# ECL.net
KiCad netlist of a schematic drawn in Altium Designer
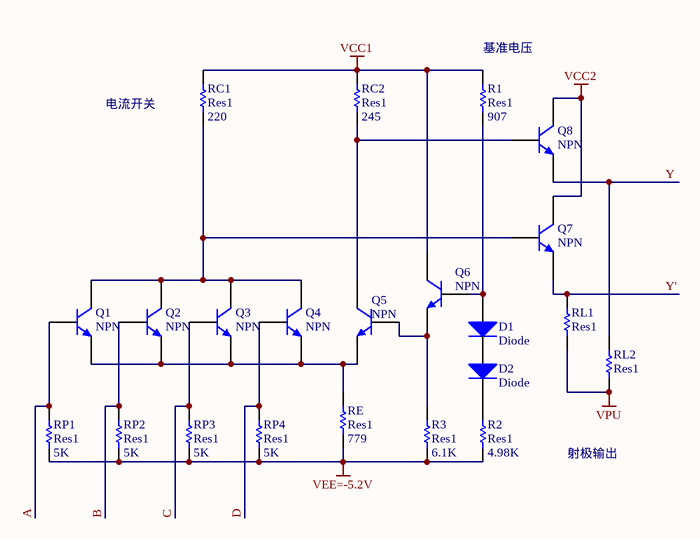
[diagram p0: ECL.SchDoc]

(export (version "E")
  (design (tool "Eeschema 10.0.6"))
  (components
    (comp (ref "D1")
      (value "Diode")
      (footprint "SMC")
      (description "Default Diode")
      (fields (field (name "PUBLISHER") "Altium Limited"))
      (libsource (lib "Miscellaneous Devices") (part "Diode"))
    )
    (comp (ref "D2")
      (value "Diode")
      (footprint "SMC")
      (description "Default Diode")
      (fields (field (name "PUBLISHER") "Altium Limited"))
      (libsource (lib "Miscellaneous Devices") (part "Diode"))
    )
    (comp (ref "Q1")
      (value "NPN")
      (footprint "TO-226-AA")
      (description "NPN Bipolar Transistor")
      (fields (field (name "PUBLISHER") "Altium Limited"))
      (libsource (lib "Miscellaneous Devices") (part "NPN"))
    )
    (comp (ref "Q2")
      (value "NPN")
      (footprint "TO-226-AA")
      (description "NPN Bipolar Transistor")
      (fields (field (name "PUBLISHER") "Altium Limited"))
      (libsource (lib "Miscellaneous Devices") (part "NPN"))
    )
    (comp (ref "Q3")
      (value "NPN")
      (footprint "TO-226-AA")
      (description "NPN Bipolar Transistor")
      (fields (field (name "PUBLISHER") "Altium Limited"))
      (libsource (lib "Miscellaneous Devices") (part "NPN"))
    )
    (comp (ref "Q4")
      (value "NPN")
      (footprint "TO-226-AA")
      (description "NPN Bipolar Transistor")
      (fields (field (name "PUBLISHER") "Altium Limited"))
      (libsource (lib "Miscellaneous Devices") (part "NPN"))
    )
    (comp (ref "Q5")
      (value "NPN")
      (footprint "TO-226-AA")
      (description "NPN Bipolar Transistor")
      (fields (field (name "PUBLISHER") "Altium Limited"))
      (libsource (lib "Miscellaneous Devices") (part "NPN"))
    )
    (comp (ref "Q6")
      (value "NPN")
      (footprint "TO-226-AA")
      (description "NPN Bipolar Transistor")
      (fields (field (name "PUBLISHER") "Altium Limited"))
      (libsource (lib "Miscellaneous Devices") (part "NPN"))
    )
    (comp (ref "Q7")
      (value "NPN")
      (footprint "TO-226-AA")
      (description "NPN Bipolar Transistor")
      (fields (field (name "PUBLISHER") "Altium Limited"))
      (libsource (lib "Miscellaneous Devices") (part "NPN"))
    )
    (comp (ref "Q8")
      (value "NPN")
      (footprint "TO-226-AA")
      (description "NPN Bipolar Transistor")
      (fields (field (name "PUBLISHER") "Altium Limited"))
      (libsource (lib "Miscellaneous Devices") (part "NPN"))
    )
    (comp (ref "R1")
      (value "Res1")
      (footprint "AXIAL-0.3")
      (description "Resistor")
      (fields (field (name "ALTIUM_VALUE") "907") (field (name "PUBLISHER") "Altium Limited"))
      (libsource (lib "Miscellaneous Devices") (part "Res1"))
    )
    (comp (ref "R2")
      (value "Res1")
      (footprint "AXIAL-0.3")
      (description "Resistor")
      (fields (field (name "ALTIUM_VALUE") "4.98K") (field (name "PUBLISHER") "Altium Limited"))
      (libsource (lib "Miscellaneous Devices") (part "Res1"))
    )
    (comp (ref "R3")
      (value "Res1")
      (footprint "AXIAL-0.3")
      (description "Resistor")
      (fields (field (name "ALTIUM_VALUE") "6.1K") (field (name "PUBLISHER") "Altium Limited"))
      (libsource (lib "Miscellaneous Devices") (part "Res1"))
    )
    (comp (ref "RC1")
      (value "Res1")
      (footprint "AXIAL-0.3")
      (description "Resistor")
      (fields (field (name "ALTIUM_VALUE") "220") (field (name "PUBLISHER") "Altium Limited"))
      (libsource (lib "Miscellaneous Devices") (part "Res1"))
    )
    (comp (ref "RC2")
      (value "Res1")
      (footprint "AXIAL-0.3")
      (description "Resistor")
      (fields (field (name "ALTIUM_VALUE") "245") (field (name "PUBLISHER") "Altium Limited"))
      (libsource (lib "Miscellaneous Devices") (part "Res1"))
    )
    (comp (ref "RE")
      (value "Res1")
      (footprint "AXIAL-0.3")
      (description "Resistor")
      (fields (field (name "ALTIUM_VALUE") "779") (field (name "PUBLISHER") "Altium Limited"))
      (libsource (lib "Miscellaneous Devices") (part "Res1"))
    )
    (comp (ref "RL1")
      (value "Res1")
      (footprint "AXIAL-0.3")
      (description "Resistor")
      (fields (field (name "PUBLISHER") "Altium Limited"))
      (libsource (lib "Miscellaneous Devices") (part "Res1"))
    )
    (comp (ref "RL2")
      (value "Res1")
      (footprint "AXIAL-0.3")
      (description "Resistor")
      (fields (field (name "PUBLISHER") "Altium Limited"))
      (libsource (lib "Miscellaneous Devices") (part "Res1"))
    )
    (comp (ref "RP1")
      (value "Res1")
      (footprint "AXIAL-0.3")
      (description "Resistor")
      (fields (field (name "ALTIUM_VALUE") "5K") (field (name "PUBLISHER") "Altium Limited"))
      (libsource (lib "Miscellaneous Devices") (part "Res1"))
    )
    (comp (ref "RP2")
      (value "Res1")
      (footprint "AXIAL-0.3")
      (description "Resistor")
      (fields (field (name "ALTIUM_VALUE") "5K") (field (name "PUBLISHER") "Altium Limited"))
      (libsource (lib "Miscellaneous Devices") (part "Res1"))
    )
    (comp (ref "RP3")
      (value "Res1")
      (footprint "AXIAL-0.3")
      (description "Resistor")
      (fields (field (name "ALTIUM_VALUE") "5K") (field (name "PUBLISHER") "Altium Limited"))
      (libsource (lib "Miscellaneous Devices") (part "Res1"))
    )
    (comp (ref "RP4")
      (value "Res1")
      (footprint "AXIAL-0.3")
      (description "Resistor")
      (fields (field (name "ALTIUM_VALUE") "5K") (field (name "PUBLISHER") "Altium Limited"))
      (libsource (lib "Miscellaneous Devices") (part "Res1"))
    )
  )
  (nets
    (net (code "1") (name "/A") (class "Default")
      (node (ref "Q1") (pin "2") (pinfunction "B_2") (pintype "passive"))
      (node (ref "RP1") (pin "2") (pinfunction "2_2") (pintype "passive"))
    )
    (net (code "2") (name "/B") (class "Default")
      (node (ref "Q2") (pin "2") (pinfunction "B_2") (pintype "passive"))
      (node (ref "RP2") (pin "2") (pinfunction "2_2") (pintype "passive"))
    )
    (net (code "3") (name "/C") (class "Default")
      (node (ref "Q3") (pin "2") (pinfunction "B_2") (pintype "passive"))
      (node (ref "RP3") (pin "2") (pinfunction "2_2") (pintype "passive"))
    )
    (net (code "4") (name "/D") (class "Default")
      (node (ref "Q4") (pin "2") (pinfunction "B_2") (pintype "passive"))
      (node (ref "RP4") (pin "2") (pinfunction "2_2") (pintype "passive"))
    )
    (net (code "5") (name "/Y") (class "Default")
      (node (ref "Q8") (pin "3") (pinfunction "E_3") (pintype "passive"))
      (node (ref "RL2") (pin "2") (pinfunction "2_2") (pintype "passive"))
    )
    (net (code "6") (name "/Y'") (class "Default")
      (node (ref "Q7") (pin "3") (pinfunction "E_3") (pintype "passive"))
      (node (ref "RL1") (pin "2") (pinfunction "2_2") (pintype "passive"))
    )
    (net (code "7") (name "Net-(D1-A)") (class "Default")
      (node (ref "D1") (pin "1") (pinfunction "A_1") (pintype "passive"))
      (node (ref "Q6") (pin "2") (pinfunction "B_2") (pintype "passive"))
      (node (ref "R1") (pin "1") (pinfunction "1_1") (pintype "passive"))
    )
    (net (code "8") (name "Net-(D2-K)") (class "Default")
      (node (ref "D2") (pin "2") (pinfunction "K_2") (pintype "passive"))
      (node (ref "R2") (pin "2") (pinfunction "2_2") (pintype "passive"))
    )
    (net (code "9") (name "Net-(Q1-C)") (class "Default")
      (node (ref "Q1") (pin "1") (pinfunction "C_1") (pintype "passive"))
      (node (ref "Q2") (pin "1") (pinfunction "C_1") (pintype "passive"))
      (node (ref "Q3") (pin "1") (pinfunction "C_1") (pintype "passive"))
      (node (ref "Q4") (pin "1") (pinfunction "C_1") (pintype "passive"))
      (node (ref "Q7") (pin "2") (pinfunction "B_2") (pintype "passive"))
      (node (ref "RC1") (pin "1") (pinfunction "1_1") (pintype "passive"))
    )
    (net (code "10") (name "Net-(Q1-E)") (class "Default")
      (node (ref "Q1") (pin "3") (pinfunction "E_3") (pintype "passive"))
      (node (ref "Q2") (pin "3") (pinfunction "E_3") (pintype "passive"))
      (node (ref "Q3") (pin "3") (pinfunction "E_3") (pintype "passive"))
      (node (ref "Q4") (pin "3") (pinfunction "E_3") (pintype "passive"))
      (node (ref "Q5") (pin "3") (pinfunction "E_3") (pintype "passive"))
      (node (ref "RE") (pin "2") (pinfunction "2_2") (pintype "passive"))
    )
    (net (code "11") (name "Net-(Q5-B)") (class "Default")
      (node (ref "Q5") (pin "2") (pinfunction "B_2") (pintype "passive"))
      (node (ref "Q6") (pin "3") (pinfunction "E_3") (pintype "passive"))
      (node (ref "R3") (pin "2") (pinfunction "2_2") (pintype "passive"))
    )
    (net (code "12") (name "Net-(Q5-C)") (class "Default")
      (node (ref "Q5") (pin "1") (pinfunction "C_1") (pintype "passive"))
      (node (ref "Q8") (pin "2") (pinfunction "B_2") (pintype "passive"))
      (node (ref "RC2") (pin "1") (pinfunction "1_1") (pintype "passive"))
    )
    (net (code "13") (name "VCC1") (class "Default")
      (node (ref "Q6") (pin "1") (pinfunction "C_1") (pintype "passive"))
      (node (ref "R1") (pin "2") (pinfunction "2_2") (pintype "passive"))
      (node (ref "RC1") (pin "2") (pinfunction "2_2") (pintype "passive"))
      (node (ref "RC2") (pin "2") (pinfunction "2_2") (pintype "passive"))
    )
    (net (code "14") (name "VCC2") (class "Default")
      (node (ref "Q7") (pin "1") (pinfunction "C_1") (pintype "passive"))
      (node (ref "Q8") (pin "1") (pinfunction "C_1") (pintype "passive"))
    )
    (net (code "15") (name "VEE=-5.2V") (class "Default")
      (node (ref "R2") (pin "1") (pinfunction "1_1") (pintype "passive"))
      (node (ref "R3") (pin "1") (pinfunction "1_1") (pintype "passive"))
      (node (ref "RE") (pin "1") (pinfunction "1_1") (pintype "passive"))
      (node (ref "RP1") (pin "1") (pinfunction "1_1") (pintype "passive"))
      (node (ref "RP2") (pin "1") (pinfunction "1_1") (pintype "passive"))
      (node (ref "RP3") (pin "1") (pinfunction "1_1") (pintype "passive"))
      (node (ref "RP4") (pin "1") (pinfunction "1_1") (pintype "passive"))
    )
    (net (code "16") (name "VPU") (class "Default")
      (node (ref "RL1") (pin "1") (pinfunction "1_1") (pintype "passive"))
      (node (ref "RL2") (pin "1") (pinfunction "1_1") (pintype "passive"))
    )
    (net (code "17") (name "unconnected-(D1-K-Pad2)") (class "Default")
      (node (ref "D1") (pin "2") (pinfunction "K_2") (pintype "passive"))
    )
    (net (code "18") (name "unconnected-(D2-A-Pad1)") (class "Default")
      (node (ref "D2") (pin "1") (pinfunction "A_1") (pintype "passive"))
    )
  )
)
